# MPU9250.net
KiCad netlist of a schematic drawn in Altium Designer
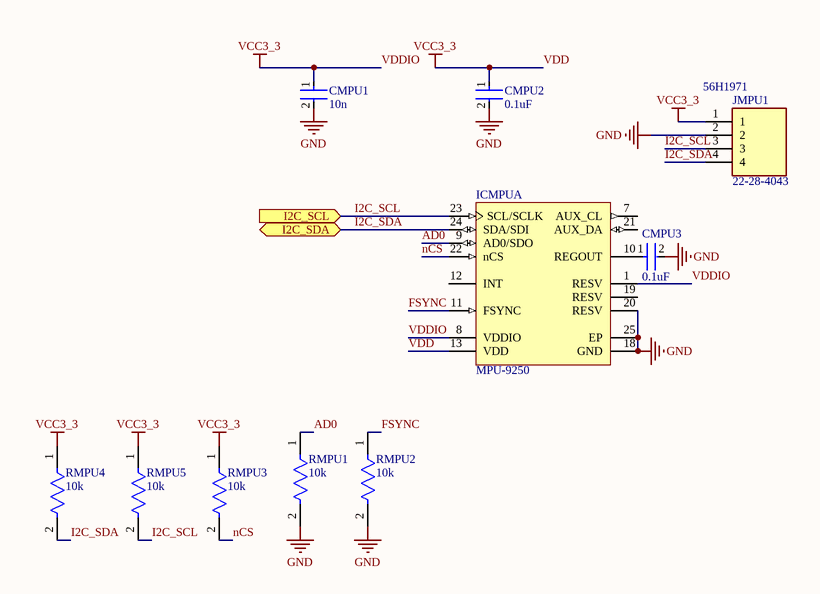
[diagram p0: MPU9250.SchDoc]

(export (version "E")
  (design (tool "Eeschema 10.0.6"))
  (components
    (comp (ref "CMPU1")
      (value "10n")
      (footprint "FP-CL10-IPC_A")
      (description "Cap Ceramic 10nF 50V X7R ±10% Pad SMD 0603 +125°C T/R")
      (fields (field (name "TOLERANCE") "10%") (field (name "VOLTAGE") "50V"))
      (libsource (lib "Altium Content Vault") (part "b4654b650e69147ec39a6b967a45e02"))
    )
    (comp (ref "CMPU2")
      (value "0.1uF")
      (footprint "FP-CL10-IPC_C")
      (description "Cap Ceramic 100nF 50V X7R ±20% Pad SMD 0603 +125°C T/R")
      (fields (field (name "TOLERANCE") "20%"))
      (libsource (lib "Altium Content Vault") (part "b4654b650e69147ec39a6b967a45e02"))
    )
    (comp (ref "CMPU3")
      (value "0.1uF")
      (footprint "FP-CL10-IPC_C")
      (description "Cap Ceramic 100nF 50V X7R ±20% Pad SMD 0603 +125°C T/R")
      (fields (field (name "TOLERANCE") "20%"))
      (libsource (lib "Altium Content Vault") (part "b4654b650e69147ec39a6b967a45e02"))
    )
    (comp (ref "ICMPU")
      (value "MPU-9250")
      (footprint "INSE-QFN-24-1700X1540TP_M")
      (description "9-axis MotionTracking device, 2.4 to 3,6 V, -40 to 85 degC, 24-Pin QFN, RoHS, Tape and Reel")
      (fields (field (name "MANUFACTURER") "InvenSense"))
      (libsource (lib "James Whitehead") (part "INSE-MPU-9250-QFN-24"))
    )
    (comp (ref "JMPU1")
      (value "22-28-4043")
      (footprint "SamacSys:HDRV4W87P0X254_1X4_1016X249X863P")
      (description "Connector")
      (fields
        (field (name "MOUSER PART NUMBER") "538-22-28-4043")
        (field (name "SUPPLIER PART NUMBER 1") "56H1971")
      )
      (libsource (lib "*") (part "22-28-4043"))
    )
    (comp (ref "RMPU1")
      (value "10k")
      (footprint "FP-ERJ3G-IPC_C")
      (description "RES SMD 10K OHM 5% 1/10W 0603")
      (fields (field (name "TOLERANCE") "5%"))
      (libsource (lib "Altium Content Vault") (part "1029c3af85768c4190bb7ad29bc67b5"))
    )
    (comp (ref "RMPU2")
      (value "10k")
      (footprint "FP-ERJ3G-IPC_C")
      (description "RES SMD 10K OHM 5% 1/10W 0603")
      (fields (field (name "TOLERANCE") "5%"))
      (libsource (lib "Altium Content Vault") (part "1029c3af85768c4190bb7ad29bc67b5"))
    )
    (comp (ref "RMPU3")
      (value "10k")
      (footprint "FP-ERJ3G-IPC_C")
      (description "RES SMD 10K OHM 5% 1/10W 0603")
      (fields (field (name "TOLERANCE") "5%"))
      (libsource (lib "Altium Content Vault") (part "1029c3af85768c4190bb7ad29bc67b5"))
    )
    (comp (ref "RMPU4")
      (value "10k")
      (footprint "FP-ERJ3G-IPC_C")
      (description "RES SMD 10K OHM 5% 1/10W 0603")
      (fields (field (name "TOLERANCE") "5%"))
      (libsource (lib "Altium Content Vault") (part "1029c3af85768c4190bb7ad29bc67b5"))
    )
    (comp (ref "RMPU5")
      (value "10k")
      (footprint "FP-ERJ3G-IPC_C")
      (description "RES SMD 10K OHM 5% 1/10W 0603")
      (fields (field (name "TOLERANCE") "5%"))
      (libsource (lib "Altium Content Vault") (part "1029c3af85768c4190bb7ad29bc67b5"))
    )
  )
  (nets
    (net (code "1") (name "/AD0") (class "Default")
      (node (ref "ICMPU") (pin "9") (pinfunction "AD0/SDO_9") (pintype "bidirectional"))
      (node (ref "RMPU1") (pin "1") (pinfunction "1_1") (pintype "passive"))
    )
    (net (code "2") (name "/FSYNC") (class "Default")
      (node (ref "ICMPU") (pin "11") (pinfunction "FSYNC_11") (pintype "input"))
      (node (ref "RMPU2") (pin "1") (pinfunction "1_1") (pintype "passive"))
    )
    (net (code "3") (name "/I2C_SCL") (class "Default")
      (node (ref "ICMPU") (pin "23") (pinfunction "SCL/SCLK_23") (pintype "input"))
      (node (ref "JMPU1") (pin "3") (pinfunction "3_3") (pintype "passive"))
      (node (ref "RMPU5") (pin "2") (pinfunction "2_2") (pintype "passive"))
    )
    (net (code "4") (name "/I2C_SDA") (class "Default")
      (node (ref "ICMPU") (pin "24") (pinfunction "SDA/SDI_24") (pintype "bidirectional"))
      (node (ref "JMPU1") (pin "4") (pinfunction "4_4") (pintype "passive"))
      (node (ref "RMPU4") (pin "2") (pinfunction "2_2") (pintype "passive"))
    )
    (net (code "5") (name "/nCS") (class "Default")
      (node (ref "ICMPU") (pin "22") (pinfunction "nCS_22") (pintype "input"))
      (node (ref "RMPU3") (pin "2") (pinfunction "2_2") (pintype "passive"))
    )
    (net (code "6") (name "GND") (class "Default")
      (node (ref "CMPU1") (pin "2") (pinfunction "2_2") (pintype "passive"))
      (node (ref "CMPU2") (pin "2") (pinfunction "2_2") (pintype "passive"))
      (node (ref "CMPU3") (pin "2") (pinfunction "2_2") (pintype "passive"))
      (node (ref "ICMPU") (pin "18") (pinfunction "GND_18") (pintype "power_in"))
      (node (ref "ICMPU") (pin "20") (pinfunction "RESV_20") (pintype "power_in"))
      (node (ref "ICMPU") (pin "25") (pinfunction "EP_25") (pintype "passive"))
      (node (ref "JMPU1") (pin "2") (pinfunction "2_2") (pintype "passive"))
      (node (ref "RMPU1") (pin "2") (pinfunction "2_2") (pintype "passive"))
      (node (ref "RMPU2") (pin "2") (pinfunction "2_2") (pintype "passive"))
    )
    (net (code "7") (name "Net-(ICMPUA-REGOUT)") (class "Default")
      (node (ref "CMPU3") (pin "1") (pinfunction "1_1") (pintype "passive"))
      (node (ref "ICMPU") (pin "10") (pinfunction "REGOUT_10") (pintype "passive"))
    )
    (net (code "8") (name "VCC3_3") (class "Default")
      (node (ref "CMPU1") (pin "1") (pinfunction "1_1") (pintype "passive"))
      (node (ref "CMPU2") (pin "1") (pinfunction "1_1") (pintype "passive"))
      (node (ref "ICMPU") (pin "1") (pinfunction "RESV_1") (pintype "power_in"))
      (node (ref "ICMPU") (pin "13") (pinfunction "VDD_13") (pintype "power_in"))
      (node (ref "ICMPU") (pin "8") (pinfunction "VDDIO_8") (pintype "power_in"))
      (node (ref "JMPU1") (pin "1") (pinfunction "1_1") (pintype "passive"))
      (node (ref "RMPU3") (pin "1") (pinfunction "1_1") (pintype "passive"))
      (node (ref "RMPU4") (pin "1") (pinfunction "1_1") (pintype "passive"))
      (node (ref "RMPU5") (pin "1") (pinfunction "1_1") (pintype "passive"))
    )
    (net (code "9") (name "unconnected-(ICMPUA-AUX_CL-Pad7)") (class "Default")
      (node (ref "ICMPU") (pin "7") (pinfunction "AUX_CL_7") (pintype "output"))
    )
    (net (code "10") (name "unconnected-(ICMPUA-AUX_DA-Pad21)") (class "Default")
      (node (ref "ICMPU") (pin "21") (pinfunction "AUX_DA_21") (pintype "bidirectional"))
    )
    (net (code "11") (name "unconnected-(ICMPUA-INT-Pad12)") (class "Default")
      (node (ref "ICMPU") (pin "12") (pinfunction "INT_12") (pintype "tri_state"))
    )
    (net (code "12") (name "unconnected-(ICMPUA-RESV-Pad19)") (class "Default")
      (node (ref "ICMPU") (pin "19") (pinfunction "RESV_19") (pintype "passive"))
    )
  )
)
